# Current-Sense-Sheet.net
KiCad netlist of a schematic drawn in Altium Designer
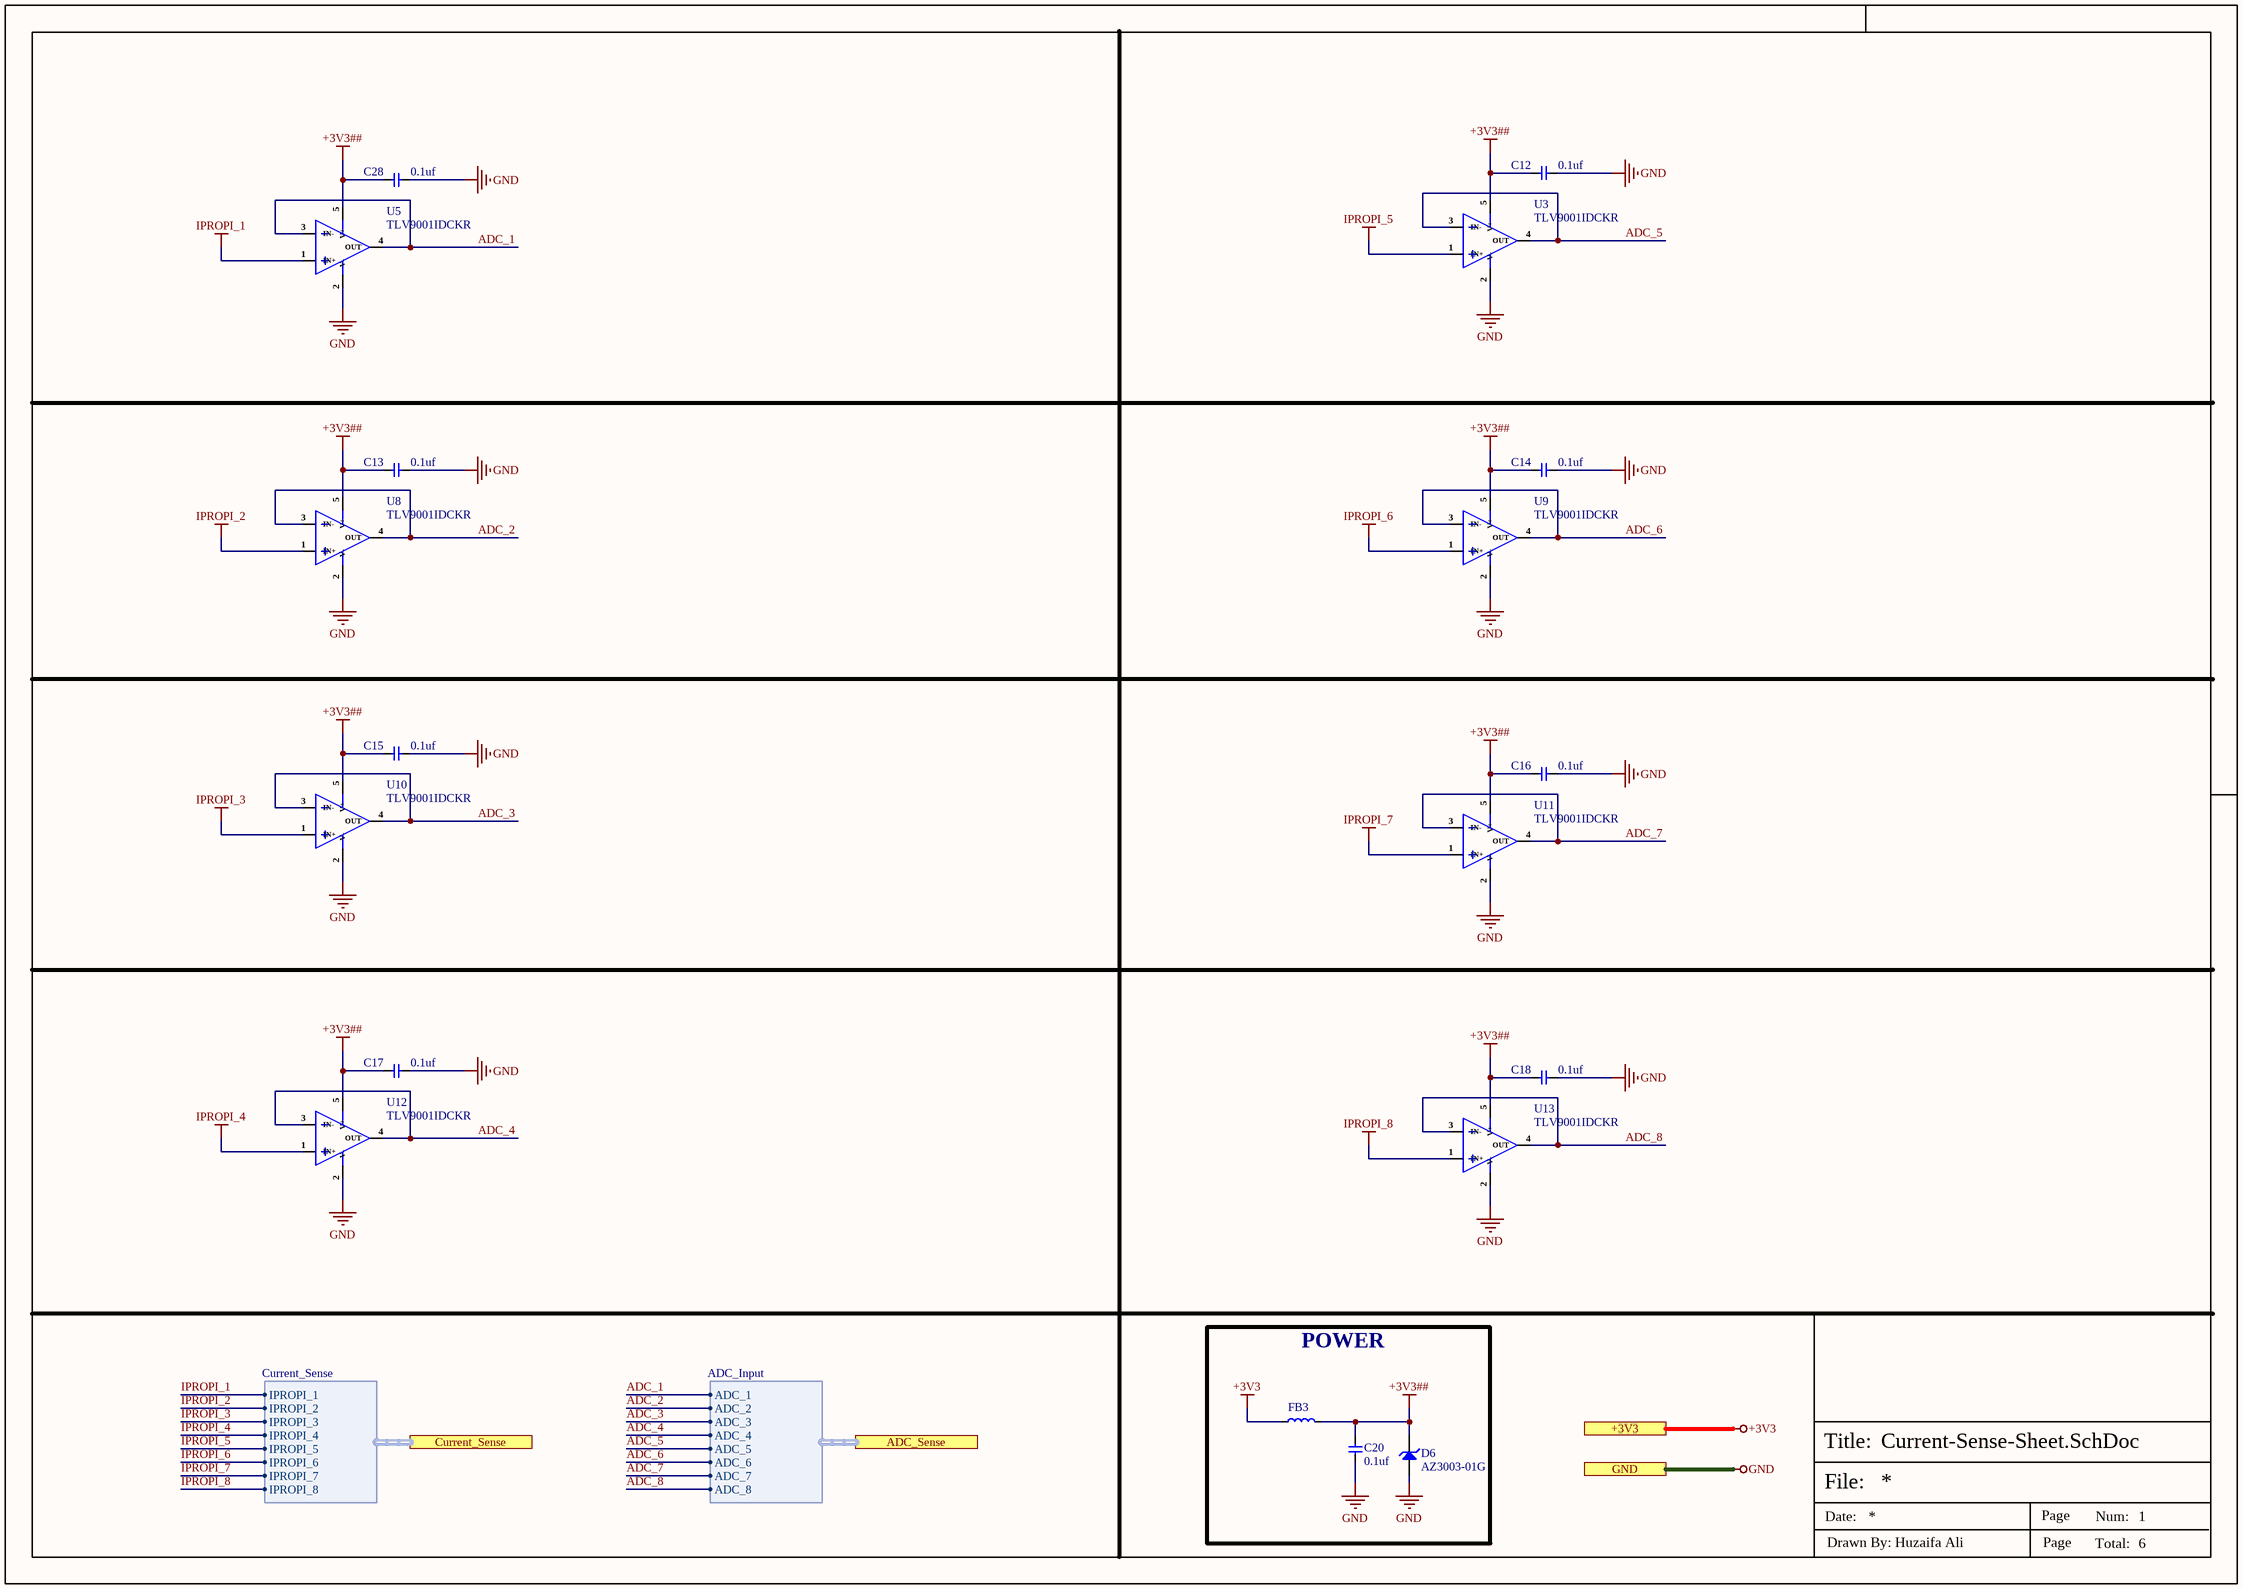
[diagram p0: Current-Sense-Sheet.SchDoc]

(export (version "E")
  (design (tool "Eeschema 10.0.6"))
  (components
    (comp (ref "C12")
      (value "0.1uf")
      (footprint "Cap-0402")
      (description "CAP CER 0.1UF 100V X5R 0402")
      (fields
        (field (name "MANUFACTURER") "Murata")
        (field (name "MANUFACTURER PART NUMBER") "GRM155R62A104KE14D")
      )
      (libsource (lib "eSpark Libraries") (part "GRM155R62A104KE14D"))
    )
    (comp (ref "C13")
      (value "0.1uf")
      (footprint "Cap-0402")
      (description "CAP CER 0.1UF 100V X5R 0402")
      (fields
        (field (name "MANUFACTURER") "Murata")
        (field (name "MANUFACTURER PART NUMBER") "GRM155R62A104KE14D")
      )
      (libsource (lib "eSpark Libraries") (part "GRM155R62A104KE14D"))
    )
    (comp (ref "C14")
      (value "0.1uf")
      (footprint "Cap-0402")
      (description "CAP CER 0.1UF 100V X5R 0402")
      (fields
        (field (name "MANUFACTURER") "Murata")
        (field (name "MANUFACTURER PART NUMBER") "GRM155R62A104KE14D")
      )
      (libsource (lib "eSpark Libraries") (part "GRM155R62A104KE14D"))
    )
    (comp (ref "C15")
      (value "0.1uf")
      (footprint "Cap-0402")
      (description "CAP CER 0.1UF 100V X5R 0402")
      (fields
        (field (name "MANUFACTURER") "Murata")
        (field (name "MANUFACTURER PART NUMBER") "GRM155R62A104KE14D")
      )
      (libsource (lib "eSpark Libraries") (part "GRM155R62A104KE14D"))
    )
    (comp (ref "C16")
      (value "0.1uf")
      (footprint "Cap-0402")
      (description "CAP CER 0.1UF 100V X5R 0402")
      (fields
        (field (name "MANUFACTURER") "Murata")
        (field (name "MANUFACTURER PART NUMBER") "GRM155R62A104KE14D")
      )
      (libsource (lib "eSpark Libraries") (part "GRM155R62A104KE14D"))
    )
    (comp (ref "C17")
      (value "0.1uf")
      (footprint "Cap-0402")
      (description "CAP CER 0.1UF 100V X5R 0402")
      (fields
        (field (name "MANUFACTURER") "Murata")
        (field (name "MANUFACTURER PART NUMBER") "GRM155R62A104KE14D")
      )
      (libsource (lib "eSpark Libraries") (part "GRM155R62A104KE14D"))
    )
    (comp (ref "C18")
      (value "0.1uf")
      (footprint "Cap-0402")
      (description "CAP CER 0.1UF 100V X5R 0402")
      (fields
        (field (name "MANUFACTURER") "Murata")
        (field (name "MANUFACTURER PART NUMBER") "GRM155R62A104KE14D")
      )
      (libsource (lib "eSpark Libraries") (part "GRM155R62A104KE14D"))
    )
    (comp (ref "C20")
      (value "0.1uf")
      (footprint "Cap-0402")
      (description "CAP CER 0.1UF 100V X5R 0402")
      (fields
        (field (name "MANUFACTURER") "Murata")
        (field (name "MANUFACTURER PART NUMBER") "GRM155R62A104KE14D")
      )
      (libsource (lib "eSpark Libraries") (part "GRM155R62A104KE14D"))
    )
    (comp (ref "C28")
      (value "0.1uf")
      (footprint "Cap-0402")
      (description "CAP CER 0.1UF 100V X5R 0402")
      (fields
        (field (name "MANUFACTURER") "Murata")
        (field (name "MANUFACTURER PART NUMBER") "GRM155R62A104KE14D")
      )
      (libsource (lib "eSpark Libraries") (part "GRM155R62A104KE14D"))
    )
    (comp (ref "D6")
      (value "AZ3003-01G")
      (footprint "SOD-123")
      (description "TVS SURGE PROTECTOR 1-CH 3.3V")
      (fields (field (name "MANUFACTURER") "Amazing"))
      (libsource (lib "eSpark Libraries") (part "AZ3003-01G"))
    )
    (comp (ref "FB3")
      (value "BLM15PG100SN1D")
      (footprint "IND-0402")
      (description "FERRITE BEAD 10 OHM 0402 1LN")
      (fields (field (name "MANUFACTURER") "Murata") (field (name "TOLERANCE") "25%"))
      (libsource (lib "eSpark Libraries") (part "BLM15PG100SN1D"))
    )
    (comp (ref "U3")
      (value "TLV9001IDCKR")
      (footprint "SC-70-5")
      (description "IC CMOS 1 CIRCUIT SC70-5")
      (fields (field (name "MANUFACTURER") "Texas Instruments") (field (name "LCSC PART NUMBER") "C398362"))
      (libsource (lib "eSpark Libraries") (part "TLV9001IDCKR"))
    )
    (comp (ref "U5")
      (value "TLV9001IDCKR")
      (footprint "SC-70-5")
      (description "IC CMOS 1 CIRCUIT SC70-5")
      (fields (field (name "MANUFACTURER") "Texas Instruments") (field (name "LCSC PART NUMBER") "C398362"))
      (libsource (lib "eSpark Libraries") (part "TLV9001IDCKR"))
    )
    (comp (ref "U8")
      (value "TLV9001IDCKR")
      (footprint "SC-70-5")
      (description "IC CMOS 1 CIRCUIT SC70-5")
      (fields (field (name "MANUFACTURER") "Texas Instruments") (field (name "LCSC PART NUMBER") "C398362"))
      (libsource (lib "eSpark Libraries") (part "TLV9001IDCKR"))
    )
    (comp (ref "U9")
      (value "TLV9001IDCKR")
      (footprint "SC-70-5")
      (description "IC CMOS 1 CIRCUIT SC70-5")
      (fields (field (name "MANUFACTURER") "Texas Instruments") (field (name "LCSC PART NUMBER") "C398362"))
      (libsource (lib "eSpark Libraries") (part "TLV9001IDCKR"))
    )
    (comp (ref "U10")
      (value "TLV9001IDCKR")
      (footprint "SC-70-5")
      (description "IC CMOS 1 CIRCUIT SC70-5")
      (fields (field (name "MANUFACTURER") "Texas Instruments") (field (name "LCSC PART NUMBER") "C398362"))
      (libsource (lib "eSpark Libraries") (part "TLV9001IDCKR"))
    )
    (comp (ref "U11")
      (value "TLV9001IDCKR")
      (footprint "SC-70-5")
      (description "IC CMOS 1 CIRCUIT SC70-5")
      (fields (field (name "MANUFACTURER") "Texas Instruments") (field (name "LCSC PART NUMBER") "C398362"))
      (libsource (lib "eSpark Libraries") (part "TLV9001IDCKR"))
    )
    (comp (ref "U12")
      (value "TLV9001IDCKR")
      (footprint "SC-70-5")
      (description "IC CMOS 1 CIRCUIT SC70-5")
      (fields (field (name "MANUFACTURER") "Texas Instruments") (field (name "LCSC PART NUMBER") "C398362"))
      (libsource (lib "eSpark Libraries") (part "TLV9001IDCKR"))
    )
    (comp (ref "U13")
      (value "TLV9001IDCKR")
      (footprint "SC-70-5")
      (description "IC CMOS 1 CIRCUIT SC70-5")
      (fields (field (name "MANUFACTURER") "Texas Instruments") (field (name "LCSC PART NUMBER") "C398362"))
      (libsource (lib "eSpark Libraries") (part "TLV9001IDCKR"))
    )
  )
  (nets
    (net (code "3") (name "+3V3") (class "Default")
      (node (ref "FB3") (pin "1") (pinfunction "1_1") (pintype "passive"))
    )
    (net (code "4") (name "+3V3##") (class "Default")
      (node (ref "C12") (pin "1") (pinfunction "1_1") (pintype "passive"))
      (node (ref "C13") (pin "1") (pinfunction "1_1") (pintype "passive"))
      (node (ref "C14") (pin "1") (pinfunction "1_1") (pintype "passive"))
      (node (ref "C15") (pin "1") (pinfunction "1_1") (pintype "passive"))
      (node (ref "C16") (pin "1") (pinfunction "1_1") (pintype "passive"))
      (node (ref "C17") (pin "1") (pinfunction "1_1") (pintype "passive"))
      (node (ref "C18") (pin "1") (pinfunction "1_1") (pintype "passive"))
      (node (ref "C20") (pin "2") (pinfunction "2_2") (pintype "passive"))
      (node (ref "C28") (pin "1") (pinfunction "1_1") (pintype "passive"))
      (node (ref "D6") (pin "2") (pinfunction "K_2") (pintype "passive"))
      (node (ref "FB3") (pin "2") (pinfunction "2_2") (pintype "passive"))
      (node (ref "U10") (pin "5") (pinfunction "V+_5") (pintype "power_in"))
      (node (ref "U11") (pin "5") (pinfunction "V+_5") (pintype "power_in"))
      (node (ref "U12") (pin "5") (pinfunction "V+_5") (pintype "power_in"))
      (node (ref "U13") (pin "5") (pinfunction "V+_5") (pintype "power_in"))
      (node (ref "U3") (pin "5") (pinfunction "V+_5") (pintype "power_in"))
      (node (ref "U5") (pin "5") (pinfunction "V+_5") (pintype "power_in"))
      (node (ref "U8") (pin "5") (pinfunction "V+_5") (pintype "power_in"))
      (node (ref "U9") (pin "5") (pinfunction "V+_5") (pintype "power_in"))
    )
    (net (code "5") (name "/ADC_1") (class "Default")
      (node (ref "U5") (pin "3") (pinfunction "IN-_3") (pintype "passive"))
      (node (ref "U5") (pin "4") (pinfunction "OUT_4") (pintype "passive"))
    )
    (net (code "6") (name "/ADC_2") (class "Default")
      (node (ref "U8") (pin "3") (pinfunction "IN-_3") (pintype "passive"))
      (node (ref "U8") (pin "4") (pinfunction "OUT_4") (pintype "passive"))
    )
    (net (code "7") (name "/ADC_3") (class "Default")
      (node (ref "U10") (pin "3") (pinfunction "IN-_3") (pintype "passive"))
      (node (ref "U10") (pin "4") (pinfunction "OUT_4") (pintype "passive"))
    )
    (net (code "8") (name "/ADC_4") (class "Default")
      (node (ref "U12") (pin "3") (pinfunction "IN-_3") (pintype "passive"))
      (node (ref "U12") (pin "4") (pinfunction "OUT_4") (pintype "passive"))
    )
    (net (code "9") (name "/ADC_5") (class "Default")
      (node (ref "U3") (pin "3") (pinfunction "IN-_3") (pintype "passive"))
      (node (ref "U3") (pin "4") (pinfunction "OUT_4") (pintype "passive"))
    )
    (net (code "10") (name "/ADC_6") (class "Default")
      (node (ref "U9") (pin "3") (pinfunction "IN-_3") (pintype "passive"))
      (node (ref "U9") (pin "4") (pinfunction "OUT_4") (pintype "passive"))
    )
    (net (code "11") (name "/ADC_7") (class "Default")
      (node (ref "U11") (pin "3") (pinfunction "IN-_3") (pintype "passive"))
      (node (ref "U11") (pin "4") (pinfunction "OUT_4") (pintype "passive"))
    )
    (net (code "12") (name "/ADC_8") (class "Default")
      (node (ref "U13") (pin "3") (pinfunction "IN-_3") (pintype "passive"))
      (node (ref "U13") (pin "4") (pinfunction "OUT_4") (pintype "passive"))
    )
    (net (code "15") (name "GND") (class "Default")
      (node (ref "C12") (pin "2") (pinfunction "2_2") (pintype "passive"))
      (node (ref "C13") (pin "2") (pinfunction "2_2") (pintype "passive"))
      (node (ref "C14") (pin "2") (pinfunction "2_2") (pintype "passive"))
      (node (ref "C15") (pin "2") (pinfunction "2_2") (pintype "passive"))
      (node (ref "C16") (pin "2") (pinfunction "2_2") (pintype "passive"))
      (node (ref "C17") (pin "2") (pinfunction "2_2") (pintype "passive"))
      (node (ref "C18") (pin "2") (pinfunction "2_2") (pintype "passive"))
      (node (ref "C20") (pin "1") (pinfunction "1_1") (pintype "passive"))
      (node (ref "C28") (pin "2") (pinfunction "2_2") (pintype "passive"))
      (node (ref "D6") (pin "1") (pinfunction "A_1") (pintype "passive"))
      (node (ref "U10") (pin "2") (pinfunction "V-_2") (pintype "power_in"))
      (node (ref "U11") (pin "2") (pinfunction "V-_2") (pintype "power_in"))
      (node (ref "U12") (pin "2") (pinfunction "V-_2") (pintype "power_in"))
      (node (ref "U13") (pin "2") (pinfunction "V-_2") (pintype "power_in"))
      (node (ref "U3") (pin "2") (pinfunction "V-_2") (pintype "power_in"))
      (node (ref "U5") (pin "2") (pinfunction "V-_2") (pintype "power_in"))
      (node (ref "U8") (pin "2") (pinfunction "V-_2") (pintype "power_in"))
      (node (ref "U9") (pin "2") (pinfunction "V-_2") (pintype "power_in"))
    )
    (net (code "16") (name "IPROPI_1") (class "Default")
      (node (ref "U5") (pin "1") (pinfunction "IN+_1") (pintype "passive"))
    )
    (net (code "17") (name "IPROPI_2") (class "Default")
      (node (ref "U8") (pin "1") (pinfunction "IN+_1") (pintype "passive"))
    )
    (net (code "18") (name "IPROPI_3") (class "Default")
      (node (ref "U10") (pin "1") (pinfunction "IN+_1") (pintype "passive"))
    )
    (net (code "19") (name "IPROPI_4") (class "Default")
      (node (ref "U12") (pin "1") (pinfunction "IN+_1") (pintype "passive"))
    )
    (net (code "20") (name "IPROPI_5") (class "Default")
      (node (ref "U3") (pin "1") (pinfunction "IN+_1") (pintype "passive"))
    )
    (net (code "21") (name "IPROPI_6") (class "Default")
      (node (ref "U9") (pin "1") (pinfunction "IN+_1") (pintype "passive"))
    )
    (net (code "22") (name "IPROPI_7") (class "Default")
      (node (ref "U11") (pin "1") (pinfunction "IN+_1") (pintype "passive"))
    )
    (net (code "23") (name "IPROPI_8") (class "Default")
      (node (ref "U13") (pin "1") (pinfunction "IN+_1") (pintype "passive"))
    )
  )
)
